# 3V_SPI_Oled_Rev1_1.net
KiCad netlist of a schematic drawn in Altium Designer
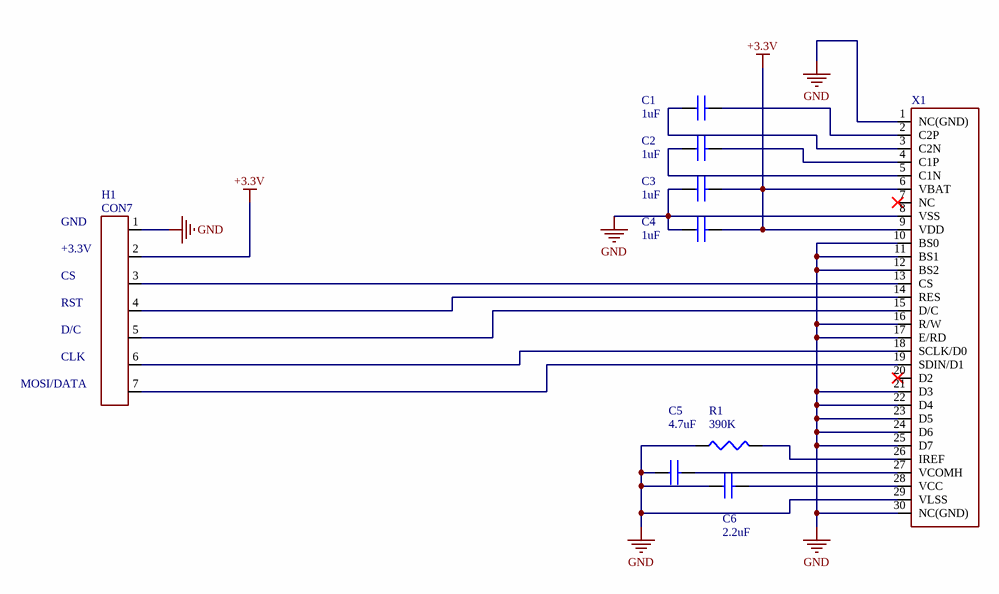
[diagram p0: 3V_SPI_Oled_Rev1.1.SchDoc]

(export (version "E")
  (design (tool "Eeschema 10.0.6"))
  (components
    (comp (ref "C1")
      (value "1uF")
      (footprint "CAPC1608X90N")
      (description "CAP 0603")
      (libsource (lib "Parts_Library") (part "CAP_0603"))
    )
    (comp (ref "C2")
      (value "1uF")
      (footprint "CAPC1608X90N")
      (description "CAP 0603")
      (libsource (lib "Parts_Library") (part "CAP_0603"))
    )
    (comp (ref "C3")
      (value "1uF")
      (footprint "CAPC1608X90N")
      (description "CAP 0603")
      (libsource (lib "Parts_Library") (part "CAP_0603"))
    )
    (comp (ref "C4")
      (value "1uF")
      (footprint "CAPC1608X90N")
      (description "CAP 0603")
      (libsource (lib "Parts_Library") (part "CAP_0603"))
    )
    (comp (ref "C5")
      (value "4.7uF")
      (footprint "CAPC1608X90N")
      (description "CAP 0603")
      (libsource (lib "Parts_Library") (part "CAP_0603"))
    )
    (comp (ref "C6")
      (value "2.2uF")
      (footprint "CAPC1608X90N")
      (description "CAP 0603")
      (libsource (lib "Parts_Library") (part "CAP_0603"))
    )
    (comp (ref "H1")
      (value "CON7")
      (footprint "HDR1X7")
      (description "CONN HEADER 7POS .100\" PADS")
      (fields (field (name "PARTNUMBER") "PADS"))
      (libsource (lib "MAR") (part "CON7"))
    )
    (comp (ref "R1")
      (value "390K")
      (footprint "RESC1608X55N")
      (description "RES 0603")
      (libsource (lib "Parts_Library") (part "RES_0603"))
    )
    (comp (ref "X1")
      (value "OLED_GLASS")
      (footprint "OLED_GLASS")
      (libsource (lib "Parts_Library") (part "OLED_GLASS"))
    )
  )
  (nets
    (net (code "1") (name "+3.3V") (class "Default")
      (node (ref "C3") (pin "2") (pinfunction "2_2") (pintype "passive"))
      (node (ref "C4") (pin "2") (pinfunction "2_2") (pintype "passive"))
      (node (ref "H1") (pin "2") (pintype "passive"))
      (node (ref "X1") (pin "6") (pinfunction "VBAT_6") (pintype "passive"))
      (node (ref "X1") (pin "9") (pinfunction "VDD_9") (pintype "passive"))
    )
    (net (code "2") (name "GND") (class "Default")
      (node (ref "C3") (pin "1") (pinfunction "1_1") (pintype "passive"))
      (node (ref "C4") (pin "1") (pinfunction "1_1") (pintype "passive"))
      (node (ref "C5") (pin "1") (pinfunction "1_1") (pintype "passive"))
      (node (ref "C6") (pin "1") (pinfunction "1_1") (pintype "passive"))
      (node (ref "H1") (pin "1") (pintype "passive"))
      (node (ref "R1") (pin "1") (pinfunction "1_1") (pintype "passive"))
      (node (ref "X1") (pin "1") (pinfunction "NC(GND)_1") (pintype "passive"))
      (node (ref "X1") (pin "10") (pinfunction "BS0_10") (pintype "passive"))
      (node (ref "X1") (pin "11") (pinfunction "BS1_11") (pintype "passive"))
      (node (ref "X1") (pin "12") (pinfunction "BS2_12") (pintype "passive"))
      (node (ref "X1") (pin "16") (pinfunction "R/W_16") (pintype "passive"))
      (node (ref "X1") (pin "17") (pinfunction "E/RD_17") (pintype "passive"))
      (node (ref "X1") (pin "21") (pinfunction "D3_21") (pintype "passive"))
      (node (ref "X1") (pin "22") (pinfunction "D4_22") (pintype "passive"))
      (node (ref "X1") (pin "23") (pinfunction "D5_23") (pintype "passive"))
      (node (ref "X1") (pin "24") (pinfunction "D6_24") (pintype "passive"))
      (node (ref "X1") (pin "25") (pinfunction "D7_25") (pintype "passive"))
      (node (ref "X1") (pin "29") (pinfunction "VLSS_29") (pintype "passive"))
      (node (ref "X1") (pin "30") (pinfunction "NC(GND)_30") (pintype "passive"))
      (node (ref "X1") (pin "8") (pinfunction "VSS_8") (pintype "passive"))
    )
    (net (code "3") (name "Net-(X1-C1N)") (class "Default")
      (node (ref "C2") (pin "1") (pinfunction "1_1") (pintype "passive"))
      (node (ref "X1") (pin "5") (pinfunction "C1N_5") (pintype "passive"))
    )
    (net (code "4") (name "Net-(X1-C1P)") (class "Default")
      (node (ref "C2") (pin "2") (pinfunction "2_2") (pintype "passive"))
      (node (ref "X1") (pin "4") (pinfunction "C1P_4") (pintype "passive"))
    )
    (net (code "5") (name "Net-(X1-C2N)") (class "Default")
      (node (ref "C1") (pin "1") (pinfunction "1_1") (pintype "passive"))
      (node (ref "X1") (pin "3") (pinfunction "C2N_3") (pintype "passive"))
    )
    (net (code "6") (name "Net-(X1-C2P)") (class "Default")
      (node (ref "C1") (pin "2") (pinfunction "2_2") (pintype "passive"))
      (node (ref "X1") (pin "2") (pinfunction "C2P_2") (pintype "passive"))
    )
    (net (code "7") (name "Net-(X1-CS)") (class "Default")
      (node (ref "H1") (pin "3") (pintype "passive"))
      (node (ref "X1") (pin "13") (pinfunction "CS_13") (pintype "passive"))
    )
    (net (code "8") (name "Net-(X1-D{slash}C)") (class "Default")
      (node (ref "H1") (pin "5") (pintype "passive"))
      (node (ref "X1") (pin "15") (pinfunction "D/C_15") (pintype "passive"))
    )
    (net (code "9") (name "Net-(X1-IREF)") (class "Default")
      (node (ref "R1") (pin "2") (pinfunction "2_2") (pintype "passive"))
      (node (ref "X1") (pin "26") (pinfunction "IREF_26") (pintype "passive"))
    )
    (net (code "10") (name "Net-(X1-RES)") (class "Default")
      (node (ref "H1") (pin "4") (pintype "passive"))
      (node (ref "X1") (pin "14") (pinfunction "RES_14") (pintype "passive"))
    )
    (net (code "11") (name "Net-(X1-SCLK{slash}D0)") (class "Default")
      (node (ref "H1") (pin "6") (pintype "passive"))
      (node (ref "X1") (pin "18") (pinfunction "SCLK/D0_18") (pintype "passive"))
    )
    (net (code "12") (name "Net-(X1-SDIN{slash}D1)") (class "Default")
      (node (ref "H1") (pin "7") (pintype "passive"))
      (node (ref "X1") (pin "19") (pinfunction "SDIN/D1_19") (pintype "passive"))
    )
    (net (code "13") (name "Net-(X1-VCC)") (class "Default")
      (node (ref "C6") (pin "2") (pinfunction "2_2") (pintype "passive"))
      (node (ref "X1") (pin "28") (pinfunction "VCC_28") (pintype "passive"))
    )
    (net (code "14") (name "Net-(X1-VCOMH)") (class "Default")
      (node (ref "C5") (pin "2") (pinfunction "2_2") (pintype "passive"))
      (node (ref "X1") (pin "27") (pinfunction "VCOMH_27") (pintype "passive"))
    )
    (net (code "15") (name "unconnected-(X1-D2-Pad20)") (class "Default")
      (node (ref "X1") (pin "20") (pinfunction "D2_20") (pintype "passive+no_connect"))
    )
    (net (code "16") (name "unconnected-(X1-NC-Pad7)") (class "Default")
      (node (ref "X1") (pin "7") (pinfunction "NC_7") (pintype "passive+no_connect"))
    )
  )
)
